# MUX.net
KiCad netlist of a schematic drawn in EAGLE
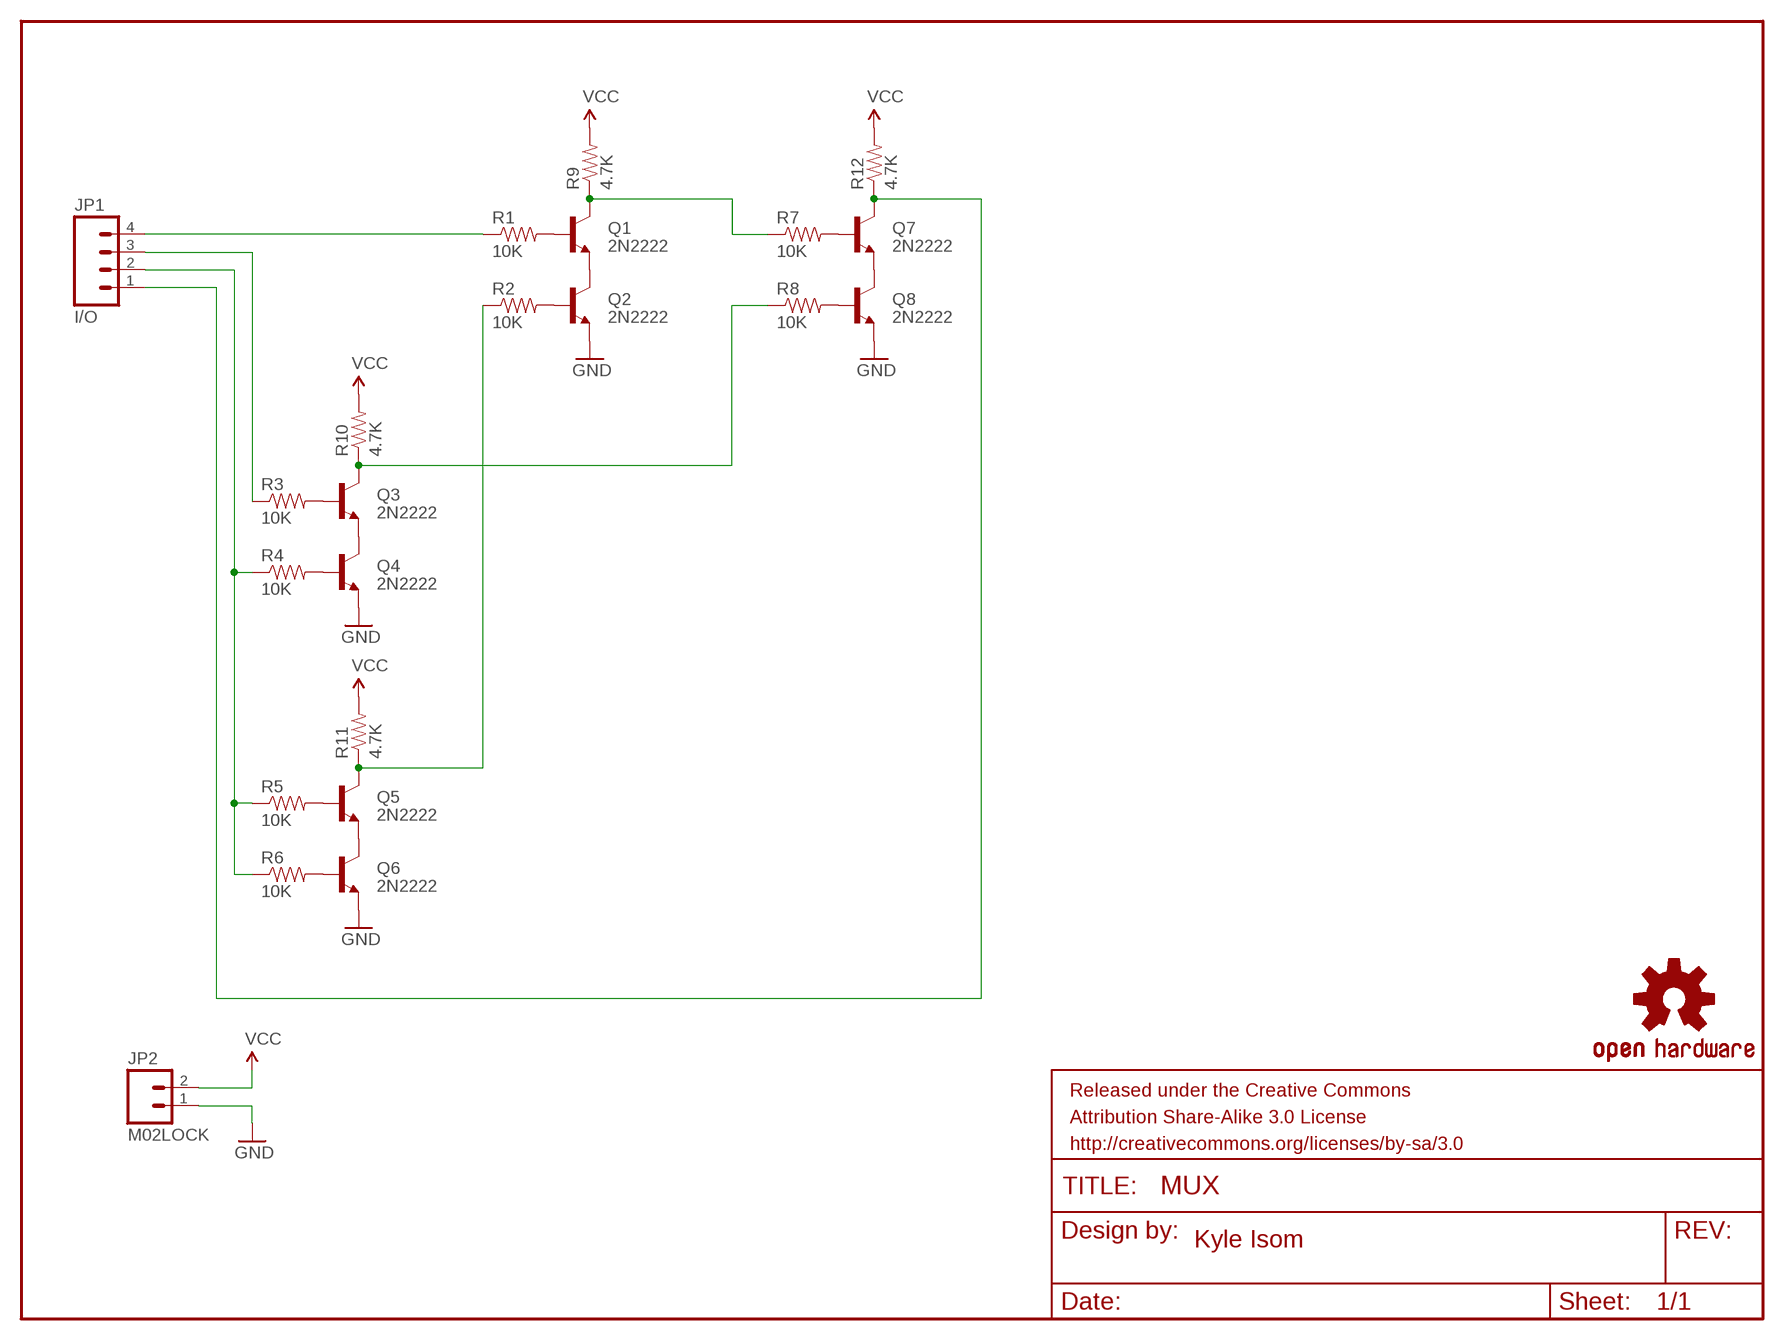
[diagram p0: schematic, sheet 1]

(export (version "E")
  (design (tool "Eeschema 10.0.6"))
  (components
    (comp (ref "FRAME1")
      (value "FRAME-LETTER")
      (footprint "eagle-import:CREATIVE_COMMONS")
      (libsource (lib "eagle-import") (part "FRAME-LETTER"))
    )
    (comp (ref "JP1")
      (value "I/O")
      (footprint "eagle-import:1X04_LOCK")
      (libsource (lib "eagle-import") (part "M04LOCK"))
    )
    (comp (ref "JP2")
      (value "M02LOCK")
      (footprint "eagle-import:1X02_LOCK")
      (libsource (lib "eagle-import") (part "M02LOCK"))
    )
    (comp (ref "LOGO1")
      (value "OSHW-LOGOS")
      (footprint "eagle-import:OSHW-LOGO-S")
      (libsource (lib "eagle-import") (part "OSHW-LOGOS"))
    )
    (comp (ref "Q1")
      (value "2N2222")
      (footprint "eagle-import:TO-92-AMMO")
      (libsource (lib "eagle-import") (part "TRANSISTOR_NPNTO-92-AMMO"))
    )
    (comp (ref "Q2")
      (value "2N2222")
      (footprint "eagle-import:TO-92-AMMO")
      (libsource (lib "eagle-import") (part "TRANSISTOR_NPNTO-92-AMMO"))
    )
    (comp (ref "Q3")
      (value "2N2222")
      (footprint "eagle-import:TO-92-AMMO")
      (libsource (lib "eagle-import") (part "TRANSISTOR_NPNTO-92-AMMO"))
    )
    (comp (ref "Q4")
      (value "2N2222")
      (footprint "eagle-import:TO-92-AMMO")
      (libsource (lib "eagle-import") (part "TRANSISTOR_NPNTO-92-AMMO"))
    )
    (comp (ref "Q5")
      (value "2N2222")
      (footprint "eagle-import:TO-92-AMMO")
      (libsource (lib "eagle-import") (part "TRANSISTOR_NPNTO-92-AMMO"))
    )
    (comp (ref "Q6")
      (value "2N2222")
      (footprint "eagle-import:TO-92-AMMO")
      (libsource (lib "eagle-import") (part "TRANSISTOR_NPNTO-92-AMMO"))
    )
    (comp (ref "Q7")
      (value "2N2222")
      (footprint "eagle-import:TO-92-AMMO")
      (libsource (lib "eagle-import") (part "TRANSISTOR_NPNTO-92-AMMO"))
    )
    (comp (ref "Q8")
      (value "2N2222")
      (footprint "eagle-import:TO-92-AMMO")
      (libsource (lib "eagle-import") (part "TRANSISTOR_NPNTO-92-AMMO"))
    )
    (comp (ref "R1")
      (value "10K")
      (footprint "eagle-import:AXIAL-0.4")
      (libsource (lib "eagle-import") (part "RESISTORPTH-1/4W"))
    )
    (comp (ref "R2")
      (value "10K")
      (footprint "eagle-import:AXIAL-0.4")
      (libsource (lib "eagle-import") (part "RESISTORPTH-1/4W"))
    )
    (comp (ref "R3")
      (value "10K")
      (footprint "eagle-import:AXIAL-0.4")
      (libsource (lib "eagle-import") (part "RESISTORPTH-1/4W"))
    )
    (comp (ref "R4")
      (value "10K")
      (footprint "eagle-import:AXIAL-0.4")
      (libsource (lib "eagle-import") (part "RESISTORPTH-1/4W"))
    )
    (comp (ref "R5")
      (value "10K")
      (footprint "eagle-import:AXIAL-0.4")
      (libsource (lib "eagle-import") (part "RESISTORPTH-1/4W"))
    )
    (comp (ref "R6")
      (value "10K")
      (footprint "eagle-import:AXIAL-0.4")
      (libsource (lib "eagle-import") (part "RESISTORPTH-1/4W"))
    )
    (comp (ref "R7")
      (value "10K")
      (footprint "eagle-import:AXIAL-0.4")
      (libsource (lib "eagle-import") (part "RESISTORPTH-1/4W"))
    )
    (comp (ref "R8")
      (value "10K")
      (footprint "eagle-import:AXIAL-0.4")
      (libsource (lib "eagle-import") (part "RESISTORPTH-1/4W"))
    )
    (comp (ref "R9")
      (value "4.7K")
      (footprint "eagle-import:AXIAL-0.4")
      (libsource (lib "eagle-import") (part "RESISTORPTH-1/4W"))
    )
    (comp (ref "R10")
      (value "4.7K")
      (footprint "eagle-import:AXIAL-0.4")
      (libsource (lib "eagle-import") (part "RESISTORPTH-1/4W"))
    )
    (comp (ref "R11")
      (value "4.7K")
      (footprint "eagle-import:AXIAL-0.4")
      (libsource (lib "eagle-import") (part "RESISTORPTH-1/4W"))
    )
    (comp (ref "R12")
      (value "4.7K")
      (footprint "eagle-import:AXIAL-0.4")
      (libsource (lib "eagle-import") (part "RESISTORPTH-1/4W"))
    )
  )
  (nets
    (net (code "1") (name "GND") (class "Default")
      (node (ref "JP2") (pin "1") (pinfunction "1_1") (pintype "passive"))
      (node (ref "Q2") (pin "1") (pinfunction "E_1") (pintype "passive"))
      (node (ref "Q4") (pin "1") (pinfunction "E_1") (pintype "passive"))
      (node (ref "Q6") (pin "1") (pinfunction "E_1") (pintype "passive"))
      (node (ref "Q8") (pin "1") (pinfunction "E_1") (pintype "passive"))
    )
    (net (code "2") (name "Net-(Q1-B)") (class "Default")
      (node (ref "Q1") (pin "2") (pinfunction "B_2") (pintype "passive"))
      (node (ref "R1") (pin "P$2") (pinfunction "2_P$2") (pintype "passive"))
    )
    (net (code "3") (name "Net-(Q1-C)") (class "Default")
      (node (ref "Q1") (pin "3") (pinfunction "C_3") (pintype "passive"))
      (node (ref "R7") (pin "P$1") (pinfunction "1_P$1") (pintype "passive"))
      (node (ref "R9") (pin "P$1") (pinfunction "1_P$1") (pintype "passive"))
    )
    (net (code "4") (name "Net-(Q1-E)") (class "Default")
      (node (ref "Q1") (pin "1") (pinfunction "E_1") (pintype "passive"))
      (node (ref "Q2") (pin "3") (pinfunction "C_3") (pintype "passive"))
    )
    (net (code "5") (name "Net-(Q2-B)") (class "Default")
      (node (ref "Q2") (pin "2") (pinfunction "B_2") (pintype "passive"))
      (node (ref "R2") (pin "P$2") (pinfunction "2_P$2") (pintype "passive"))
    )
    (net (code "6") (name "Net-(Q3-B)") (class "Default")
      (node (ref "Q3") (pin "2") (pinfunction "B_2") (pintype "passive"))
      (node (ref "R3") (pin "P$2") (pinfunction "2_P$2") (pintype "passive"))
    )
    (net (code "7") (name "Net-(Q3-C)") (class "Default")
      (node (ref "Q3") (pin "3") (pinfunction "C_3") (pintype "passive"))
      (node (ref "R10") (pin "P$1") (pinfunction "1_P$1") (pintype "passive"))
      (node (ref "R8") (pin "P$1") (pinfunction "1_P$1") (pintype "passive"))
    )
    (net (code "8") (name "Net-(Q3-E)") (class "Default")
      (node (ref "Q3") (pin "1") (pinfunction "E_1") (pintype "passive"))
      (node (ref "Q4") (pin "3") (pinfunction "C_3") (pintype "passive"))
    )
    (net (code "9") (name "Net-(Q4-B)") (class "Default")
      (node (ref "Q4") (pin "2") (pinfunction "B_2") (pintype "passive"))
      (node (ref "R4") (pin "P$2") (pinfunction "2_P$2") (pintype "passive"))
    )
    (net (code "10") (name "Net-(Q5-B)") (class "Default")
      (node (ref "Q5") (pin "2") (pinfunction "B_2") (pintype "passive"))
      (node (ref "R5") (pin "P$2") (pinfunction "2_P$2") (pintype "passive"))
    )
    (net (code "11") (name "Net-(Q5-C)") (class "Default")
      (node (ref "Q5") (pin "3") (pinfunction "C_3") (pintype "passive"))
      (node (ref "R11") (pin "P$1") (pinfunction "1_P$1") (pintype "passive"))
      (node (ref "R2") (pin "P$1") (pinfunction "1_P$1") (pintype "passive"))
    )
    (net (code "12") (name "Net-(Q5-E)") (class "Default")
      (node (ref "Q5") (pin "1") (pinfunction "E_1") (pintype "passive"))
      (node (ref "Q6") (pin "3") (pinfunction "C_3") (pintype "passive"))
    )
    (net (code "13") (name "Net-(Q6-B)") (class "Default")
      (node (ref "Q6") (pin "2") (pinfunction "B_2") (pintype "passive"))
      (node (ref "R6") (pin "P$2") (pinfunction "2_P$2") (pintype "passive"))
    )
    (net (code "14") (name "Net-(Q7-B)") (class "Default")
      (node (ref "Q7") (pin "2") (pinfunction "B_2") (pintype "passive"))
      (node (ref "R7") (pin "P$2") (pinfunction "2_P$2") (pintype "passive"))
    )
    (net (code "15") (name "Net-(Q7-C)") (class "Default")
      (node (ref "JP1") (pin "1") (pinfunction "1_1") (pintype "passive"))
      (node (ref "Q7") (pin "3") (pinfunction "C_3") (pintype "passive"))
      (node (ref "R12") (pin "P$1") (pinfunction "1_P$1") (pintype "passive"))
    )
    (net (code "16") (name "Net-(Q7-E)") (class "Default")
      (node (ref "Q7") (pin "1") (pinfunction "E_1") (pintype "passive"))
      (node (ref "Q8") (pin "3") (pinfunction "C_3") (pintype "passive"))
    )
    (net (code "17") (name "Net-(Q8-B)") (class "Default")
      (node (ref "Q8") (pin "2") (pinfunction "B_2") (pintype "passive"))
      (node (ref "R8") (pin "P$2") (pinfunction "2_P$2") (pintype "passive"))
    )
    (net (code "18") (name "Net-(R1-1)") (class "Default")
      (node (ref "JP1") (pin "4") (pinfunction "4_4") (pintype "passive"))
      (node (ref "R1") (pin "P$1") (pinfunction "1_P$1") (pintype "passive"))
    )
    (net (code "19") (name "Net-(R3-1)") (class "Default")
      (node (ref "JP1") (pin "3") (pinfunction "3_3") (pintype "passive"))
      (node (ref "R3") (pin "P$1") (pinfunction "1_P$1") (pintype "passive"))
    )
    (net (code "20") (name "Net-(R4-1)") (class "Default")
      (node (ref "JP1") (pin "2") (pinfunction "2_2") (pintype "passive"))
      (node (ref "R4") (pin "P$1") (pinfunction "1_P$1") (pintype "passive"))
      (node (ref "R5") (pin "P$1") (pinfunction "1_P$1") (pintype "passive"))
      (node (ref "R6") (pin "P$1") (pinfunction "1_P$1") (pintype "passive"))
    )
    (net (code "21") (name "VCC") (class "Default")
      (node (ref "JP2") (pin "2") (pinfunction "2_2") (pintype "passive"))
      (node (ref "R10") (pin "P$2") (pinfunction "2_P$2") (pintype "passive"))
      (node (ref "R11") (pin "P$2") (pinfunction "2_P$2") (pintype "passive"))
      (node (ref "R12") (pin "P$2") (pinfunction "2_P$2") (pintype "passive"))
      (node (ref "R9") (pin "P$2") (pinfunction "2_P$2") (pintype "passive"))
    )
  )
)
